# Sheet1.net
KiCad netlist of a schematic drawn in Altium Designer
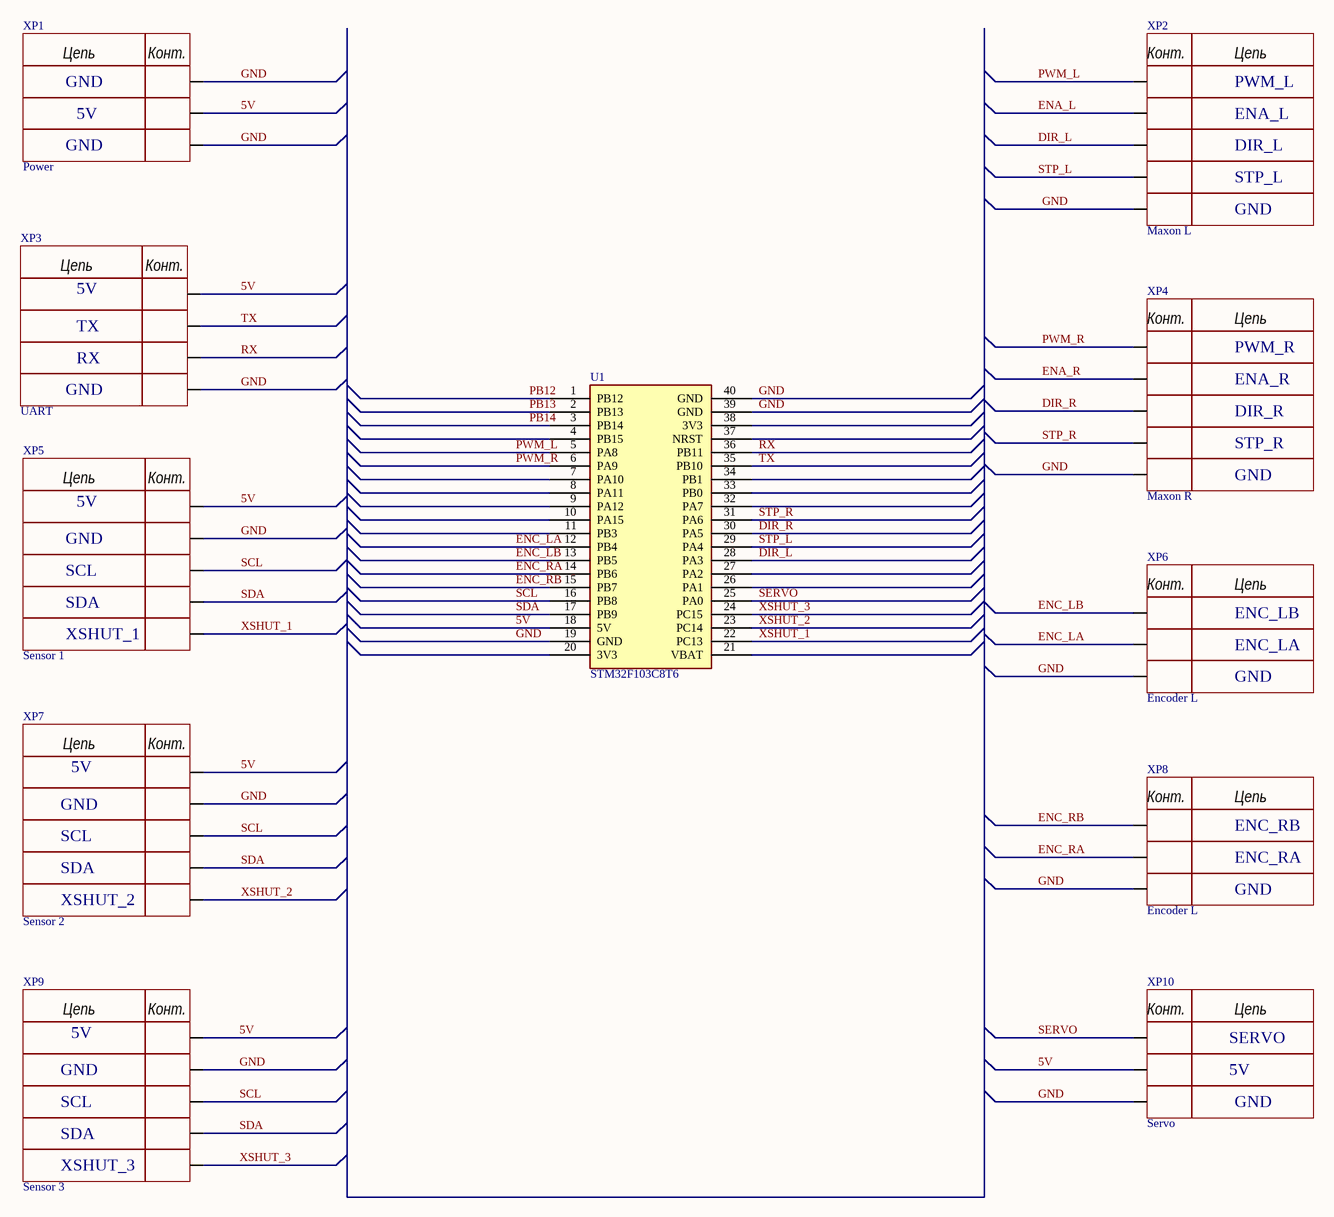
[diagram p0: Sheet1.SchDoc]

(export (version "E")
  (design (tool "Eeschema 10.0.6"))
  (components
    (comp (ref "U1")
      (value "STM32F103C8T6")
      (footprint "Stm32 BluePill")
      (description "Designed By @Alixahedi")
      (libsource (lib "Schlib1") (part "BluePill"))
    )
    (comp (ref "XP1")
      (value "Power")
      (footprint "B3B-PH-K-S")
      (fields (field (name "MANUFACTURER") "JST Corporation"))
      (libsource (lib "") (part "B3B-PH-K-S_1"))
    )
    (comp (ref "XP2") (value "Maxon L") (footprint "B5B-PH-K-S") (libsource (lib "") (part "B5B-PH-K-S_1")))
    (comp (ref "XP3")
      (value "UART")
      (footprint "PcbLib1:B4B-PH-K-S")
      (fields (field (name "MANUFACTURER") "JST Corporation"))
      (libsource (lib "Schlib1") (part "B4B-PH-K-S"))
    )
    (comp (ref "XP4") (value "Maxon R") (footprint "B5B-PH-K-S") (libsource (lib "") (part "B5B-PH-K-S_1")))
    (comp (ref "XP5")
      (value "Sensor 1")
      (footprint "B5B-PH-K-S")
      (libsource (lib "Schlib1") (part "B5B-PH-K-S"))
    )
    (comp (ref "XP6")
      (value "Encoder L")
      (footprint "B3B-PH-K-S")
      (fields (field (name "MANUFACTURER") "JST Corporation"))
      (libsource (lib "Schlib1") (part "B3B-PH-K-S"))
    )
    (comp (ref "XP7")
      (value "Sensor 2")
      (footprint "B5B-PH-K-S")
      (libsource (lib "Schlib1") (part "B5B-PH-K-S"))
    )
    (comp (ref "XP8")
      (value "Encoder L")
      (footprint "B3B-PH-K-S")
      (fields (field (name "MANUFACTURER") "JST Corporation"))
      (libsource (lib "Schlib1") (part "B3B-PH-K-S"))
    )
    (comp (ref "XP9")
      (value "Sensor 3")
      (footprint "B5B-PH-K-S")
      (libsource (lib "Schlib1") (part "B5B-PH-K-S"))
    )
    (comp (ref "XP10")
      (value "Servo")
      (footprint "B3B-PH-K-S")
      (fields (field (name "MANUFACTURER") "JST Corporation"))
      (libsource (lib "Schlib1") (part "B3B-PH-K-S"))
    )
  )
  (nets
    (net (code "1") (name "/5V") (class "Default")
      (node (ref "U1") (pin "18") (pinfunction "5V_18") (pintype "passive"))
      (node (ref "XP1") (pin "2") (pinfunction "2_2") (pintype "passive"))
      (node (ref "XP10") (pin "2") (pinfunction "2_2") (pintype "passive"))
      (node (ref "XP3") (pin "1") (pinfunction "1_1") (pintype "passive"))
      (node (ref "XP5") (pin "1") (pinfunction "1_1") (pintype "passive"))
      (node (ref "XP7") (pin "1") (pinfunction "1_1") (pintype "passive"))
      (node (ref "XP9") (pin "1") (pinfunction "1_1") (pintype "passive"))
    )
    (net (code "2") (name "/DIR_L") (class "Default")
      (node (ref "U1") (pin "28") (pinfunction "PA3_28") (pintype "passive"))
      (node (ref "XP2") (pin "3") (pinfunction "3_3") (pintype "passive"))
    )
    (net (code "3") (name "/DIR_R") (class "Default")
      (node (ref "U1") (pin "30") (pinfunction "PA5_30") (pintype "passive"))
      (node (ref "XP4") (pin "3") (pinfunction "3_3") (pintype "passive"))
    )
    (net (code "4") (name "/ENA_L") (class "Default")
      (node (ref "XP2") (pin "2") (pinfunction "2_2") (pintype "passive"))
    )
    (net (code "5") (name "/ENA_R") (class "Default")
      (node (ref "XP4") (pin "2") (pinfunction "2_2") (pintype "passive"))
    )
    (net (code "6") (name "/ENC_LA") (class "Default")
      (node (ref "U1") (pin "12") (pinfunction "PB4_12") (pintype "passive"))
      (node (ref "XP6") (pin "2") (pinfunction "2_2") (pintype "passive"))
    )
    (net (code "7") (name "/ENC_LB") (class "Default")
      (node (ref "U1") (pin "13") (pinfunction "PB5_13") (pintype "passive"))
      (node (ref "XP6") (pin "1") (pinfunction "1_1") (pintype "passive"))
    )
    (net (code "8") (name "/ENC_RA") (class "Default")
      (node (ref "U1") (pin "14") (pinfunction "PB6_14") (pintype "passive"))
      (node (ref "XP8") (pin "2") (pinfunction "2_2") (pintype "passive"))
    )
    (net (code "9") (name "/ENC_RB") (class "Default")
      (node (ref "U1") (pin "15") (pinfunction "PB7_15") (pintype "passive"))
      (node (ref "XP8") (pin "1") (pinfunction "1_1") (pintype "passive"))
    )
    (net (code "10") (name "/GND") (class "Default")
      (node (ref "U1") (pin "19") (pinfunction "GND_19") (pintype "passive"))
      (node (ref "U1") (pin "39") (pinfunction "GND_39") (pintype "passive"))
      (node (ref "U1") (pin "40") (pinfunction "GND_40") (pintype "passive"))
      (node (ref "XP1") (pin "1") (pinfunction "1_1") (pintype "passive"))
      (node (ref "XP1") (pin "3") (pinfunction "3_3") (pintype "passive"))
      (node (ref "XP10") (pin "3") (pinfunction "3_3") (pintype "passive"))
      (node (ref "XP2") (pin "5") (pinfunction "5_5") (pintype "passive"))
      (node (ref "XP3") (pin "4") (pinfunction "4_4") (pintype "passive"))
      (node (ref "XP4") (pin "5") (pinfunction "5_5") (pintype "passive"))
      (node (ref "XP5") (pin "2") (pinfunction "2_2") (pintype "passive"))
      (node (ref "XP6") (pin "3") (pinfunction "3_3") (pintype "passive"))
      (node (ref "XP7") (pin "2") (pinfunction "2_2") (pintype "passive"))
      (node (ref "XP8") (pin "3") (pinfunction "3_3") (pintype "passive"))
      (node (ref "XP9") (pin "2") (pinfunction "2_2") (pintype "passive"))
    )
    (net (code "11") (name "/PB12") (class "Default")
      (node (ref "U1") (pin "1") (pinfunction "PB12_1") (pintype "passive"))
    )
    (net (code "12") (name "/PB13") (class "Default")
      (node (ref "U1") (pin "2") (pinfunction "PB13_2") (pintype "passive"))
    )
    (net (code "13") (name "/PB14") (class "Default")
      (node (ref "U1") (pin "3") (pinfunction "PB14_3") (pintype "passive"))
    )
    (net (code "14") (name "/PWM_L") (class "Default")
      (node (ref "U1") (pin "5") (pinfunction "PA8_5") (pintype "passive"))
      (node (ref "XP2") (pin "1") (pinfunction "1_1") (pintype "passive"))
    )
    (net (code "15") (name "/PWM_R") (class "Default")
      (node (ref "U1") (pin "6") (pinfunction "PA9_6") (pintype "passive"))
      (node (ref "XP4") (pin "1") (pinfunction "1_1") (pintype "passive"))
    )
    (net (code "16") (name "/RX") (class "Default")
      (node (ref "U1") (pin "36") (pinfunction "PB11_36") (pintype "passive"))
      (node (ref "XP3") (pin "3") (pinfunction "3_3") (pintype "passive"))
    )
    (net (code "17") (name "/SCL") (class "Default")
      (node (ref "U1") (pin "16") (pinfunction "PB8_16") (pintype "passive"))
      (node (ref "XP5") (pin "3") (pinfunction "3_3") (pintype "passive"))
      (node (ref "XP7") (pin "3") (pinfunction "3_3") (pintype "passive"))
      (node (ref "XP9") (pin "3") (pinfunction "3_3") (pintype "passive"))
    )
    (net (code "18") (name "/SDA") (class "Default")
      (node (ref "U1") (pin "17") (pinfunction "PB9_17") (pintype "passive"))
      (node (ref "XP5") (pin "4") (pinfunction "4_4") (pintype "passive"))
      (node (ref "XP7") (pin "4") (pinfunction "4_4") (pintype "passive"))
      (node (ref "XP9") (pin "4") (pinfunction "4_4") (pintype "passive"))
    )
    (net (code "19") (name "/SERVO") (class "Default")
      (node (ref "U1") (pin "25") (pinfunction "PA0_25") (pintype "passive"))
      (node (ref "XP10") (pin "1") (pinfunction "1_1") (pintype "passive"))
    )
    (net (code "20") (name "/STP_L") (class "Default")
      (node (ref "U1") (pin "29") (pinfunction "PA4_29") (pintype "passive"))
      (node (ref "XP2") (pin "4") (pinfunction "4_4") (pintype "passive"))
    )
    (net (code "21") (name "/STP_R") (class "Default")
      (node (ref "U1") (pin "31") (pinfunction "PA6_31") (pintype "passive"))
      (node (ref "XP4") (pin "4") (pinfunction "4_4") (pintype "passive"))
    )
    (net (code "22") (name "/TX") (class "Default")
      (node (ref "U1") (pin "35") (pinfunction "PB10_35") (pintype "passive"))
      (node (ref "XP3") (pin "2") (pinfunction "2_2") (pintype "passive"))
    )
    (net (code "23") (name "/XSHUT_1") (class "Default")
      (node (ref "U1") (pin "22") (pinfunction "PC13_22") (pintype "passive"))
      (node (ref "XP5") (pin "5") (pinfunction "5_5") (pintype "passive"))
    )
    (net (code "24") (name "/XSHUT_2") (class "Default")
      (node (ref "U1") (pin "23") (pinfunction "PC14_23") (pintype "passive"))
      (node (ref "XP7") (pin "5") (pinfunction "5_5") (pintype "passive"))
    )
    (net (code "25") (name "/XSHUT_3") (class "Default")
      (node (ref "U1") (pin "24") (pinfunction "PC15_24") (pintype "passive"))
      (node (ref "XP9") (pin "5") (pinfunction "5_5") (pintype "passive"))
    )
    (net (code "26") (name "unconnected-(U1-3V3-Pad20)") (class "Default")
      (node (ref "U1") (pin "20") (pinfunction "3V3_20") (pintype "passive"))
    )
    (net (code "27") (name "unconnected-(U1-3V3-Pad38)") (class "Default")
      (node (ref "U1") (pin "38") (pinfunction "3V3_38") (pintype "passive"))
    )
    (net (code "28") (name "unconnected-(U1-NRST-Pad37)") (class "Default")
      (node (ref "U1") (pin "37") (pinfunction "NRST_37") (pintype "passive"))
    )
    (net (code "29") (name "unconnected-(U1-PA1-Pad26)") (class "Default")
      (node (ref "U1") (pin "26") (pinfunction "PA1_26") (pintype "passive"))
    )
    (net (code "30") (name "unconnected-(U1-PA2-Pad27)") (class "Default")
      (node (ref "U1") (pin "27") (pinfunction "PA2_27") (pintype "passive"))
    )
    (net (code "31") (name "unconnected-(U1-PA7-Pad32)") (class "Default")
      (node (ref "U1") (pin "32") (pinfunction "PA7_32") (pintype "passive"))
    )
    (net (code "32") (name "unconnected-(U1-PA10-Pad7)") (class "Default")
      (node (ref "U1") (pin "7") (pinfunction "PA10_7") (pintype "passive"))
    )
    (net (code "33") (name "unconnected-(U1-PA11-Pad8)") (class "Default")
      (node (ref "U1") (pin "8") (pinfunction "PA11_8") (pintype "passive"))
    )
    (net (code "34") (name "unconnected-(U1-PA12-Pad9)") (class "Default")
      (node (ref "U1") (pin "9") (pinfunction "PA12_9") (pintype "passive"))
    )
    (net (code "35") (name "unconnected-(U1-PA15-Pad10)") (class "Default")
      (node (ref "U1") (pin "10") (pinfunction "PA15_10") (pintype "passive"))
    )
    (net (code "36") (name "unconnected-(U1-PB0-Pad33)") (class "Default")
      (node (ref "U1") (pin "33") (pinfunction "PB0_33") (pintype "passive"))
    )
    (net (code "37") (name "unconnected-(U1-PB1-Pad34)") (class "Default")
      (node (ref "U1") (pin "34") (pinfunction "PB1_34") (pintype "passive"))
    )
    (net (code "38") (name "unconnected-(U1-PB3-Pad11)") (class "Default")
      (node (ref "U1") (pin "11") (pinfunction "PB3_11") (pintype "passive"))
    )
    (net (code "39") (name "unconnected-(U1-PB15-Pad4)") (class "Default")
      (node (ref "U1") (pin "4") (pinfunction "PB15_4") (pintype "passive"))
    )
    (net (code "40") (name "unconnected-(U1-VBAT-Pad21)") (class "Default")
      (node (ref "U1") (pin "21") (pinfunction "VBAT_21") (pintype "passive"))
    )
  )
)
